# TUI.net
KiCad netlist of a schematic drawn in Altium Designer
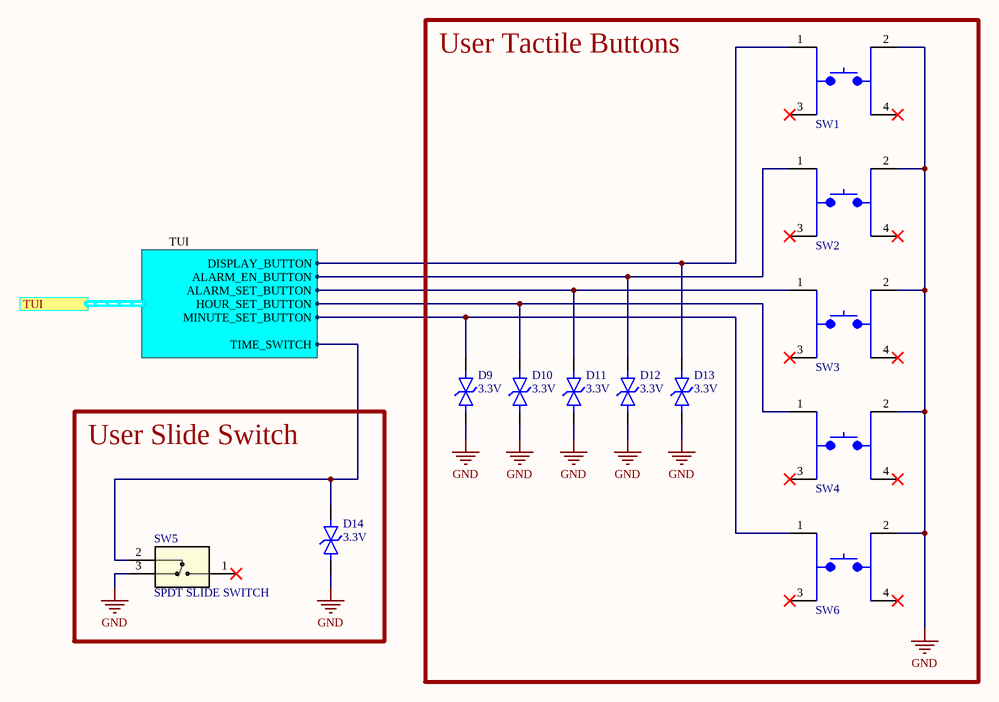
[diagram p0: TUI.SchDoc]

(export (version "E")
  (design (tool "Eeschema 10.0.6"))
  (components
    (comp (ref "D9")
      (value "DESD3V3E1BL-7B")
      (footprint "Beethoven-clock:0402-TVS")
      (description "TVS DIODE 3.3VWM 7VC DFN1006-2")
      (fields (field (name "MFR") "Diodes Incorporated") (field (name "VRS") "3.3V"))
      (libsource (lib "Beethoven-clock") (part "TVS Diode 3.3V Bi"))
    )
    (comp (ref "D10")
      (value "DESD3V3E1BL-7B")
      (footprint "Beethoven-clock:0402-TVS")
      (description "TVS DIODE 3.3VWM 7VC DFN1006-2")
      (fields (field (name "MFR") "Diodes Incorporated") (field (name "VRS") "3.3V"))
      (libsource (lib "Beethoven-clock") (part "TVS Diode 3.3V Bi"))
    )
    (comp (ref "D11")
      (value "DESD3V3E1BL-7B")
      (footprint "Beethoven-clock:0402-TVS")
      (description "TVS DIODE 3.3VWM 7VC DFN1006-2")
      (fields (field (name "MFR") "Diodes Incorporated") (field (name "VRS") "3.3V"))
      (libsource (lib "Beethoven-clock") (part "TVS Diode 3.3V Bi"))
    )
    (comp (ref "D12")
      (value "DESD3V3E1BL-7B")
      (footprint "Beethoven-clock:0402-TVS")
      (description "TVS DIODE 3.3VWM 7VC DFN1006-2")
      (fields (field (name "MFR") "Diodes Incorporated") (field (name "VRS") "3.3V"))
      (libsource (lib "Beethoven-clock") (part "TVS Diode 3.3V Bi"))
    )
    (comp (ref "D13")
      (value "DESD3V3E1BL-7B")
      (footprint "Beethoven-clock:0402-TVS")
      (description "TVS DIODE 3.3VWM 7VC DFN1006-2")
      (fields (field (name "MFR") "Diodes Incorporated") (field (name "VRS") "3.3V"))
      (libsource (lib "Beethoven-clock") (part "TVS Diode 3.3V Bi"))
    )
    (comp (ref "D14")
      (value "DESD3V3E1BL-7B")
      (footprint "Beethoven-clock:0402-TVS")
      (description "TVS DIODE 3.3VWM 7VC DFN1006-2")
      (fields (field (name "MFR") "Diodes Incorporated") (field (name "VRS") "3.3V"))
      (libsource (lib "Beethoven-clock") (part "TVS Diode 3.3V Bi"))
    )
    (comp (ref "SW1")
      (value "SPDT PUSH BUTTON SWITCH")
      (footprint "Beethoven-clock:430152080826")
      (description "SWITCH TACTILE SPST-NO 0.05A 12V")
      (fields (field (name "MFR") "Würth Elektronik"))
      (libsource (lib "Beethoven-clock") (part "SPDT PUSH BUTTON SWITCH"))
    )
    (comp (ref "SW2")
      (value "SPDT PUSH BUTTON SWITCH")
      (footprint "Beethoven-clock:430152080826")
      (description "SWITCH TACTILE SPST-NO 0.05A 12V")
      (fields (field (name "MFR") "Würth Elektronik"))
      (libsource (lib "Beethoven-clock") (part "SPDT PUSH BUTTON SWITCH"))
    )
    (comp (ref "SW3")
      (value "SPDT PUSH BUTTON SWITCH")
      (footprint "Beethoven-clock:430152080826")
      (description "SWITCH TACTILE SPST-NO 0.05A 12V")
      (fields (field (name "MFR") "Würth Elektronik"))
      (libsource (lib "Beethoven-clock") (part "SPDT PUSH BUTTON SWITCH"))
    )
    (comp (ref "SW4")
      (value "SPDT PUSH BUTTON SWITCH")
      (footprint "Beethoven-clock:430152080826")
      (description "SWITCH TACTILE SPST-NO 0.05A 12V")
      (fields (field (name "MFR") "Würth Elektronik"))
      (libsource (lib "Beethoven-clock") (part "SPDT PUSH BUTTON SWITCH"))
    )
    (comp (ref "SW5")
      (value "SPDT SLIDE SWITCH")
      (footprint "Beethoven-clock:JS102011SCQN")
      (fields (field (name "MFR") "C&K"))
      (libsource (lib "Beethoven-clock") (part "SPDT SLIDE SWITCH"))
    )
    (comp (ref "SW6")
      (value "SPDT PUSH BUTTON SWITCH")
      (footprint "Beethoven-clock:430152080826")
      (description "SWITCH TACTILE SPST-NO 0.05A 12V")
      (fields (field (name "MFR") "Würth Elektronik"))
      (libsource (lib "Beethoven-clock") (part "SPDT PUSH BUTTON SWITCH"))
    )
  )
  (nets
    (net (code "3") (name "GND") (class "Default")
      (node (ref "D10") (pin "2") (pinfunction "2_2") (pintype "passive"))
      (node (ref "D11") (pin "2") (pinfunction "2_2") (pintype "passive"))
      (node (ref "D12") (pin "2") (pinfunction "2_2") (pintype "passive"))
      (node (ref "D13") (pin "2") (pinfunction "2_2") (pintype "passive"))
      (node (ref "D14") (pin "2") (pinfunction "2_2") (pintype "passive"))
      (node (ref "D9") (pin "2") (pinfunction "2_2") (pintype "passive"))
      (node (ref "SW1") (pin "2") (pinfunction "2_2") (pintype "passive"))
      (node (ref "SW2") (pin "2") (pinfunction "2_2") (pintype "passive"))
      (node (ref "SW3") (pin "2") (pinfunction "2_2") (pintype "passive"))
      (node (ref "SW4") (pin "2") (pinfunction "2_2") (pintype "passive"))
      (node (ref "SW5") (pin "3") (pinfunction "3_3") (pintype "passive"))
      (node (ref "SW6") (pin "2") (pinfunction "2_2") (pintype "passive"))
    )
    (net (code "4") (name "Net-(D9-Pad1)") (class "Default")
      (node (ref "D9") (pin "1") (pinfunction "1_1") (pintype "passive"))
      (node (ref "SW6") (pin "1") (pinfunction "1_1") (pintype "passive"))
    )
    (net (code "5") (name "Net-(D10-Pad1)") (class "Default")
      (node (ref "D10") (pin "1") (pinfunction "1_1") (pintype "passive"))
      (node (ref "SW4") (pin "1") (pinfunction "1_1") (pintype "passive"))
    )
    (net (code "6") (name "Net-(D11-Pad1)") (class "Default")
      (node (ref "D11") (pin "1") (pinfunction "1_1") (pintype "passive"))
      (node (ref "SW3") (pin "1") (pinfunction "1_1") (pintype "passive"))
    )
    (net (code "7") (name "Net-(D12-Pad1)") (class "Default")
      (node (ref "D12") (pin "1") (pinfunction "1_1") (pintype "passive"))
      (node (ref "SW2") (pin "1") (pinfunction "1_1") (pintype "passive"))
    )
    (net (code "8") (name "Net-(D13-Pad1)") (class "Default")
      (node (ref "D13") (pin "1") (pinfunction "1_1") (pintype "passive"))
      (node (ref "SW1") (pin "1") (pinfunction "1_1") (pintype "passive"))
    )
    (net (code "9") (name "Net-(D14-Pad1)") (class "Default")
      (node (ref "D14") (pin "1") (pinfunction "1_1") (pintype "passive"))
      (node (ref "SW5") (pin "2") (pinfunction "2_2") (pintype "passive"))
    )
    (net (code "10") (name "unconnected-(SW1-Pad3)") (class "Default")
      (node (ref "SW1") (pin "3") (pinfunction "3_3") (pintype "passive+no_connect"))
    )
    (net (code "11") (name "unconnected-(SW1-Pad4)") (class "Default")
      (node (ref "SW1") (pin "4") (pinfunction "4_4") (pintype "passive+no_connect"))
    )
    (net (code "12") (name "unconnected-(SW2-Pad3)") (class "Default")
      (node (ref "SW2") (pin "3") (pinfunction "3_3") (pintype "passive+no_connect"))
    )
    (net (code "13") (name "unconnected-(SW2-Pad4)") (class "Default")
      (node (ref "SW2") (pin "4") (pinfunction "4_4") (pintype "passive+no_connect"))
    )
    (net (code "14") (name "unconnected-(SW3-Pad3)") (class "Default")
      (node (ref "SW3") (pin "3") (pinfunction "3_3") (pintype "passive+no_connect"))
    )
    (net (code "15") (name "unconnected-(SW3-Pad4)") (class "Default")
      (node (ref "SW3") (pin "4") (pinfunction "4_4") (pintype "passive+no_connect"))
    )
    (net (code "16") (name "unconnected-(SW4-Pad3)") (class "Default")
      (node (ref "SW4") (pin "3") (pinfunction "3_3") (pintype "passive+no_connect"))
    )
    (net (code "17") (name "unconnected-(SW4-Pad4)") (class "Default")
      (node (ref "SW4") (pin "4") (pinfunction "4_4") (pintype "passive+no_connect"))
    )
    (net (code "18") (name "unconnected-(SW5-Pad1)") (class "Default")
      (node (ref "SW5") (pin "1") (pinfunction "1_1") (pintype "passive+no_connect"))
    )
    (net (code "19") (name "unconnected-(SW6-Pad3)") (class "Default")
      (node (ref "SW6") (pin "3") (pinfunction "3_3") (pintype "passive+no_connect"))
    )
    (net (code "20") (name "unconnected-(SW6-Pad4)") (class "Default")
      (node (ref "SW6") (pin "4") (pinfunction "4_4") (pintype "passive+no_connect"))
    )
  )
)
